# lcd_ex.net
KiCad netlist of a schematic drawn in Altium Designer
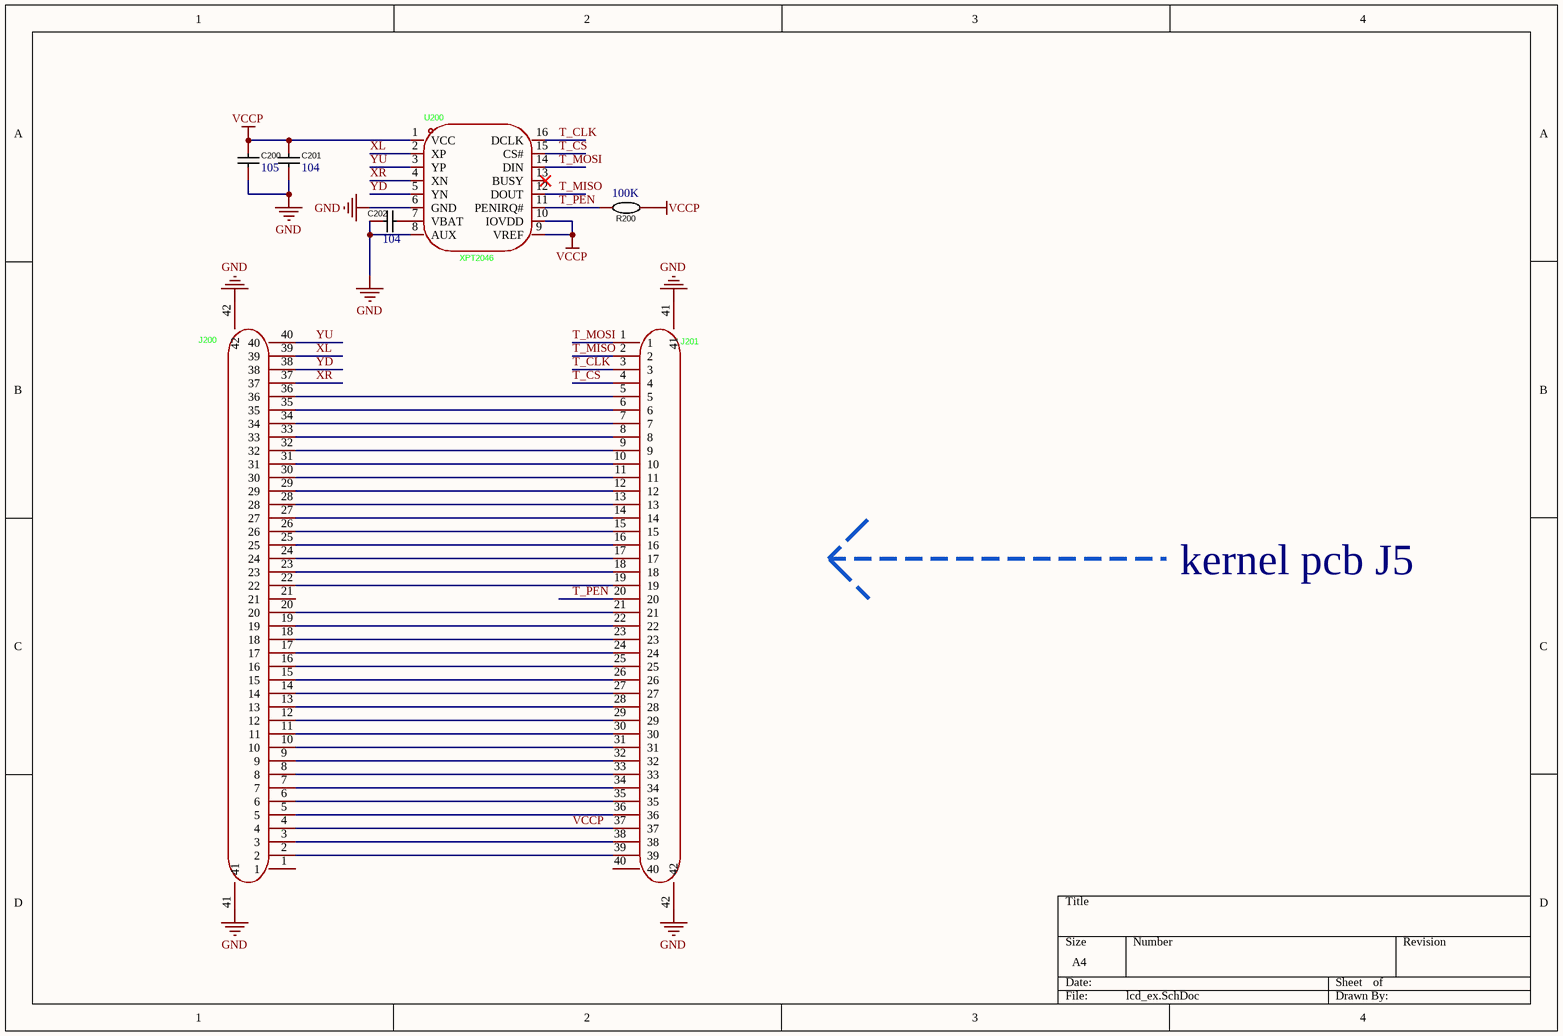
[diagram p0: lcd_ex.SchDoc]

(export (version "E")
  (design (tool "Eeschema 10.0.6"))
  (components
    (comp (ref "C200")
      (value "105")
      (footprint "0805_C")
      (description "电容100nf")
      (fields (field (name "MANUFACTURER") "FH(风华)") (field (name "MANUFACTURER PART") "0402CG200J500NT"))
      (libsource (lib "kernel") (part "0402C_104"))
    )
    (comp (ref "C201")
      (value "104")
      (footprint "0805_C")
      (description "电容100nf")
      (fields (field (name "MANUFACTURER") "FH(风华)") (field (name "MANUFACTURER PART") "0402CG200J500NT"))
      (libsource (lib "kernel") (part "0402C_104"))
    )
    (comp (ref "C202")
      (value "104")
      (footprint "0805_C")
      (description "电容100nf")
      (fields (field (name "MANUFACTURER") "FH(风华)") (field (name "MANUFACTURER PART") "0402CG200J500NT"))
      (libsource (lib "kernel") (part "0402C_104"))
    )
    (comp (ref "J200")
      (value "AFC01-S40FCA-00")
      (footprint "FPC-SMD_AFC01-S40FCA-00")
      (description "FPC")
      (fields (field (name "MANUFACTURER") "JS(钜硕电子)"))
      (libsource (lib "kernel") (part "AFC01-S40FCA-00"))
    )
    (comp (ref "J201")
      (value "AFC01-S40FCA-00")
      (footprint "FPC-SMD_AFC01-S40FCA-00")
      (description "FPC")
      (fields (field (name "MANUFACTURER") "JS(钜硕电子)"))
      (libsource (lib "kernel") (part "AFC01-S40FCA-00"))
    )
    (comp (ref "R200")
      (value "100K")
      (footprint "0805_R")
      (description "电阻100K")
      (fields
        (field (name "MANUFACTURER") "UNI-ROYAL(厚声)")
        (field (name "MANUFACTURER PART") "0402WGF1002TCE")
      )
      (libsource (lib "kernel") (part "0402WGF1003TCE"))
    )
    (comp (ref "U200")
      (value "XPT2046")
      (footprint "TSSOP-16_L5.0-W4.4-P0.65-LS6.4-BL")
      (fields (field (name "MANUFACTURER") "XPT(矽普特)"))
      (libsource (lib "lcd_ex") (part "XPT2046"))
    )
  )
  (nets
    (net (code "1") (name "/T_CLK") (class "Default")
      (node (ref "J201") (pin "3") (pinfunction "3_3") (pintype "passive"))
      (node (ref "U200") (pin "16") (pinfunction "DCLK_16") (pintype "passive"))
    )
    (net (code "2") (name "/T_CS") (class "Default")
      (node (ref "J201") (pin "4") (pinfunction "4_4") (pintype "passive"))
      (node (ref "U200") (pin "15") (pinfunction "CS#_15") (pintype "passive"))
    )
    (net (code "3") (name "/T_MISO") (class "Default")
      (node (ref "J201") (pin "2") (pinfunction "2_2") (pintype "passive"))
      (node (ref "U200") (pin "12") (pinfunction "DOUT_12") (pintype "passive"))
    )
    (net (code "4") (name "/T_MOSI") (class "Default")
      (node (ref "J201") (pin "1") (pinfunction "1_1") (pintype "passive"))
      (node (ref "U200") (pin "14") (pinfunction "DIN_14") (pintype "passive"))
    )
    (net (code "5") (name "/T_PEN") (class "Default")
      (node (ref "J201") (pin "20") (pinfunction "20_20") (pintype "passive"))
      (node (ref "R200") (pin "1") (pinfunction "1_1") (pintype "passive"))
      (node (ref "U200") (pin "11") (pinfunction "PENIRQ#_11") (pintype "passive"))
    )
    (net (code "6") (name "/XL") (class "Default")
      (node (ref "J200") (pin "39") (pinfunction "39_39") (pintype "passive"))
      (node (ref "U200") (pin "2") (pinfunction "XP_2") (pintype "passive"))
    )
    (net (code "7") (name "/XR") (class "Default")
      (node (ref "J200") (pin "37") (pinfunction "37_37") (pintype "passive"))
      (node (ref "U200") (pin "4") (pinfunction "XN_4") (pintype "passive"))
    )
    (net (code "8") (name "/YD") (class "Default")
      (node (ref "J200") (pin "38") (pinfunction "38_38") (pintype "passive"))
      (node (ref "U200") (pin "5") (pinfunction "YN_5") (pintype "passive"))
    )
    (net (code "9") (name "/YU") (class "Default")
      (node (ref "J200") (pin "40") (pinfunction "40_40") (pintype "passive"))
      (node (ref "U200") (pin "3") (pinfunction "YP_3") (pintype "passive"))
    )
    (net (code "10") (name "GND") (class "Default")
      (node (ref "C200") (pin "1") (pinfunction "1_1") (pintype "passive"))
      (node (ref "C201") (pin "1") (pinfunction "1_1") (pintype "passive"))
      (node (ref "C202") (pin "2") (pinfunction "2_2") (pintype "passive"))
      (node (ref "J200") (pin "41") (pinfunction "41_41") (pintype "passive"))
      (node (ref "J200") (pin "42") (pinfunction "42_42") (pintype "passive"))
      (node (ref "J201") (pin "41") (pinfunction "41_41") (pintype "passive"))
      (node (ref "J201") (pin "42") (pinfunction "42_42") (pintype "passive"))
      (node (ref "U200") (pin "6") (pinfunction "GND_6") (pintype "passive"))
      (node (ref "U200") (pin "8") (pinfunction "AUX_8") (pintype "passive"))
    )
    (net (code "11") (name "Net-(J200-Pad2)") (class "Default")
      (node (ref "J200") (pin "2") (pinfunction "2_2") (pintype "passive"))
      (node (ref "J201") (pin "39") (pinfunction "39_39") (pintype "passive"))
    )
    (net (code "12") (name "Net-(J200-Pad3)") (class "Default")
      (node (ref "J200") (pin "3") (pinfunction "3_3") (pintype "passive"))
      (node (ref "J201") (pin "38") (pinfunction "38_38") (pintype "passive"))
    )
    (net (code "13") (name "Net-(J200-Pad5)") (class "Default")
      (node (ref "J200") (pin "5") (pinfunction "5_5") (pintype "passive"))
      (node (ref "J201") (pin "36") (pinfunction "36_36") (pintype "passive"))
    )
    (net (code "14") (name "Net-(J200-Pad6)") (class "Default")
      (node (ref "J200") (pin "6") (pinfunction "6_6") (pintype "passive"))
      (node (ref "J201") (pin "35") (pinfunction "35_35") (pintype "passive"))
    )
    (net (code "15") (name "Net-(J200-Pad7)") (class "Default")
      (node (ref "J200") (pin "7") (pinfunction "7_7") (pintype "passive"))
      (node (ref "J201") (pin "34") (pinfunction "34_34") (pintype "passive"))
    )
    (net (code "16") (name "Net-(J200-Pad8)") (class "Default")
      (node (ref "J200") (pin "8") (pinfunction "8_8") (pintype "passive"))
      (node (ref "J201") (pin "33") (pinfunction "33_33") (pintype "passive"))
    )
    (net (code "17") (name "Net-(J200-Pad9)") (class "Default")
      (node (ref "J200") (pin "9") (pinfunction "9_9") (pintype "passive"))
      (node (ref "J201") (pin "32") (pinfunction "32_32") (pintype "passive"))
    )
    (net (code "18") (name "Net-(J200-Pad10)") (class "Default")
      (node (ref "J200") (pin "10") (pinfunction "10_10") (pintype "passive"))
      (node (ref "J201") (pin "31") (pinfunction "31_31") (pintype "passive"))
    )
    (net (code "19") (name "Net-(J200-Pad11)") (class "Default")
      (node (ref "J200") (pin "11") (pinfunction "11_11") (pintype "passive"))
      (node (ref "J201") (pin "30") (pinfunction "30_30") (pintype "passive"))
    )
    (net (code "20") (name "Net-(J200-Pad12)") (class "Default")
      (node (ref "J200") (pin "12") (pinfunction "12_12") (pintype "passive"))
      (node (ref "J201") (pin "29") (pinfunction "29_29") (pintype "passive"))
    )
    (net (code "21") (name "Net-(J200-Pad13)") (class "Default")
      (node (ref "J200") (pin "13") (pinfunction "13_13") (pintype "passive"))
      (node (ref "J201") (pin "28") (pinfunction "28_28") (pintype "passive"))
    )
    (net (code "22") (name "Net-(J200-Pad14)") (class "Default")
      (node (ref "J200") (pin "14") (pinfunction "14_14") (pintype "passive"))
      (node (ref "J201") (pin "27") (pinfunction "27_27") (pintype "passive"))
    )
    (net (code "23") (name "Net-(J200-Pad15)") (class "Default")
      (node (ref "J200") (pin "15") (pinfunction "15_15") (pintype "passive"))
      (node (ref "J201") (pin "26") (pinfunction "26_26") (pintype "passive"))
    )
    (net (code "24") (name "Net-(J200-Pad16)") (class "Default")
      (node (ref "J200") (pin "16") (pinfunction "16_16") (pintype "passive"))
      (node (ref "J201") (pin "25") (pinfunction "25_25") (pintype "passive"))
    )
    (net (code "25") (name "Net-(J200-Pad17)") (class "Default")
      (node (ref "J200") (pin "17") (pinfunction "17_17") (pintype "passive"))
      (node (ref "J201") (pin "24") (pinfunction "24_24") (pintype "passive"))
    )
    (net (code "26") (name "Net-(J200-Pad18)") (class "Default")
      (node (ref "J200") (pin "18") (pinfunction "18_18") (pintype "passive"))
      (node (ref "J201") (pin "23") (pinfunction "23_23") (pintype "passive"))
    )
    (net (code "27") (name "Net-(J200-Pad19)") (class "Default")
      (node (ref "J200") (pin "19") (pinfunction "19_19") (pintype "passive"))
      (node (ref "J201") (pin "22") (pinfunction "22_22") (pintype "passive"))
    )
    (net (code "28") (name "Net-(J200-Pad20)") (class "Default")
      (node (ref "J200") (pin "20") (pinfunction "20_20") (pintype "passive"))
      (node (ref "J201") (pin "21") (pinfunction "21_21") (pintype "passive"))
    )
    (net (code "29") (name "Net-(J200-Pad22)") (class "Default")
      (node (ref "J200") (pin "22") (pinfunction "22_22") (pintype "passive"))
      (node (ref "J201") (pin "19") (pinfunction "19_19") (pintype "passive"))
    )
    (net (code "30") (name "Net-(J200-Pad23)") (class "Default")
      (node (ref "J200") (pin "23") (pinfunction "23_23") (pintype "passive"))
      (node (ref "J201") (pin "18") (pinfunction "18_18") (pintype "passive"))
    )
    (net (code "31") (name "Net-(J200-Pad24)") (class "Default")
      (node (ref "J200") (pin "24") (pinfunction "24_24") (pintype "passive"))
      (node (ref "J201") (pin "17") (pinfunction "17_17") (pintype "passive"))
    )
    (net (code "32") (name "Net-(J200-Pad25)") (class "Default")
      (node (ref "J200") (pin "25") (pinfunction "25_25") (pintype "passive"))
      (node (ref "J201") (pin "16") (pinfunction "16_16") (pintype "passive"))
    )
    (net (code "33") (name "Net-(J200-Pad26)") (class "Default")
      (node (ref "J200") (pin "26") (pinfunction "26_26") (pintype "passive"))
      (node (ref "J201") (pin "15") (pinfunction "15_15") (pintype "passive"))
    )
    (net (code "34") (name "Net-(J200-Pad27)") (class "Default")
      (node (ref "J200") (pin "27") (pinfunction "27_27") (pintype "passive"))
      (node (ref "J201") (pin "14") (pinfunction "14_14") (pintype "passive"))
    )
    (net (code "35") (name "Net-(J200-Pad28)") (class "Default")
      (node (ref "J200") (pin "28") (pinfunction "28_28") (pintype "passive"))
      (node (ref "J201") (pin "13") (pinfunction "13_13") (pintype "passive"))
    )
    (net (code "36") (name "Net-(J200-Pad29)") (class "Default")
      (node (ref "J200") (pin "29") (pinfunction "29_29") (pintype "passive"))
      (node (ref "J201") (pin "12") (pinfunction "12_12") (pintype "passive"))
    )
    (net (code "37") (name "Net-(J200-Pad30)") (class "Default")
      (node (ref "J200") (pin "30") (pinfunction "30_30") (pintype "passive"))
      (node (ref "J201") (pin "11") (pinfunction "11_11") (pintype "passive"))
    )
    (net (code "38") (name "Net-(J200-Pad31)") (class "Default")
      (node (ref "J200") (pin "31") (pinfunction "31_31") (pintype "passive"))
      (node (ref "J201") (pin "10") (pinfunction "10_10") (pintype "passive"))
    )
    (net (code "39") (name "Net-(J200-Pad32)") (class "Default")
      (node (ref "J200") (pin "32") (pinfunction "32_32") (pintype "passive"))
      (node (ref "J201") (pin "9") (pinfunction "9_9") (pintype "passive"))
    )
    (net (code "40") (name "Net-(J200-Pad33)") (class "Default")
      (node (ref "J200") (pin "33") (pinfunction "33_33") (pintype "passive"))
      (node (ref "J201") (pin "8") (pinfunction "8_8") (pintype "passive"))
    )
    (net (code "41") (name "Net-(J200-Pad34)") (class "Default")
      (node (ref "J200") (pin "34") (pinfunction "34_34") (pintype "passive"))
      (node (ref "J201") (pin "7") (pinfunction "7_7") (pintype "passive"))
    )
    (net (code "42") (name "Net-(J200-Pad35)") (class "Default")
      (node (ref "J200") (pin "35") (pinfunction "35_35") (pintype "passive"))
      (node (ref "J201") (pin "6") (pinfunction "6_6") (pintype "passive"))
    )
    (net (code "43") (name "Net-(J200-Pad36)") (class "Default")
      (node (ref "J200") (pin "36") (pinfunction "36_36") (pintype "passive"))
      (node (ref "J201") (pin "5") (pinfunction "5_5") (pintype "passive"))
    )
    (net (code "44") (name "Net-(U200-VBAT)") (class "Default")
      (node (ref "C202") (pin "1") (pinfunction "1_1") (pintype "passive"))
      (node (ref "U200") (pin "7") (pinfunction "VBAT_7") (pintype "passive"))
    )
    (net (code "45") (name "VCCP") (class "Default")
      (node (ref "C200") (pin "2") (pinfunction "2_2") (pintype "passive"))
      (node (ref "C201") (pin "2") (pinfunction "2_2") (pintype "passive"))
      (node (ref "J200") (pin "4") (pinfunction "4_4") (pintype "passive"))
      (node (ref "J201") (pin "37") (pinfunction "37_37") (pintype "passive"))
      (node (ref "R200") (pin "2") (pinfunction "2_2") (pintype "passive"))
      (node (ref "U200") (pin "1") (pinfunction "VCC_1") (pintype "passive"))
      (node (ref "U200") (pin "10") (pinfunction "IOVDD_10") (pintype "passive"))
      (node (ref "U200") (pin "9") (pinfunction "VREF_9") (pintype "passive"))
    )
    (net (code "46") (name "unconnected-(J200-Pad1)") (class "Default")
      (node (ref "J200") (pin "1") (pinfunction "1_1") (pintype "passive"))
    )
    (net (code "47") (name "unconnected-(J200-Pad21)") (class "Default")
      (node (ref "J200") (pin "21") (pinfunction "21_21") (pintype "passive"))
    )
    (net (code "48") (name "unconnected-(J201-Pad40)") (class "Default")
      (node (ref "J201") (pin "40") (pinfunction "40_40") (pintype "passive"))
    )
    (net (code "49") (name "unconnected-(U200-BUSY-Pad13)") (class "Default")
      (node (ref "U200") (pin "13") (pinfunction "BUSY_13") (pintype "passive+no_connect"))
    )
  )
)
